# Connections.net
KiCad netlist of a schematic drawn in Altium Designer
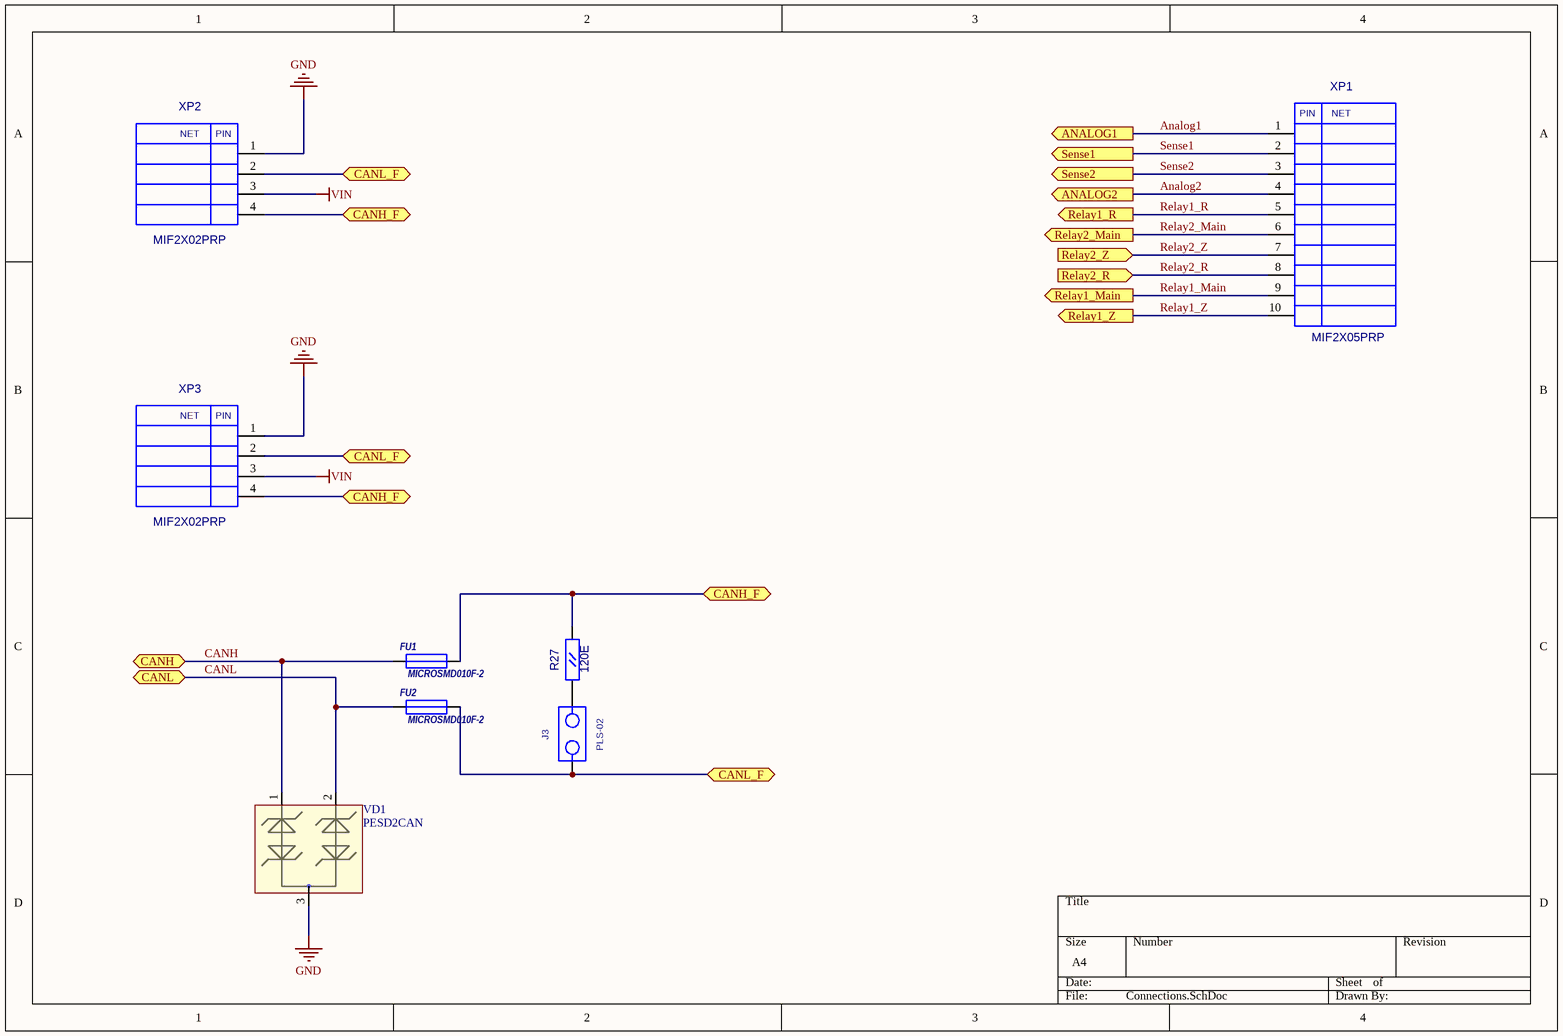
[diagram p0: Connections.SchDoc]

(export (version "E")
  (design (tool "Eeschema 10.0.6"))
  (components
    (comp (ref "FU1")
      (value "MICROSMD010F-2")
      (footprint "RC1210")
      (description "MICROSMD")
      (libsource (lib "gprs_modem_2") (part "MICROSMD"))
    )
    (comp (ref "FU2")
      (value "MICROSMD010F-2")
      (footprint "RC1210")
      (description "MICROSMD")
      (libsource (lib "gprs_modem_2") (part "MICROSMD"))
    )
    (comp (ref "J3") (value "PLS-02") (footprint "PLS-02") (libsource (lib "gprs_modem_2") (part "PLS-02")))
    (comp (ref "R27")
      (value "120E")
      (footprint "RC0805")
      (description "RC0805")
      (libsource (lib "gprs_modem_2") (part "RC0805"))
    )
    (comp (ref "VD1")
      (value "PESD2CAN")
      (footprint "SOT-23(123)")
      (description "TVS for CAN")
      (libsource (lib "gprs_modem_2") (part "PESD2CAN"))
    )
    (comp (ref "XP1")
      (value "MIF2X05PRP")
      (footprint "MIF2X05PRP")
      (libsource (lib "shlagbaum") (part "MIF2X05PRP"))
    )
    (comp (ref "XP2")
      (value "MIF2X02PRP")
      (footprint "MIF2X02PRP")
      (libsource (lib "gprs_modem_2") (part "MIF2X02PRP"))
    )
    (comp (ref "XP3")
      (value "MIF2X02PRP")
      (footprint "MIF2X02PRP")
      (libsource (lib "gprs_modem_2") (part "MIF2X02PRP"))
    )
  )
  (nets
    (net (code "1") (name "/Analog1") (class "Default")
      (node (ref "XP1") (pin "1") (pinfunction "1_1") (pintype "passive"))
    )
    (net (code "2") (name "/Analog2") (class "Default")
      (node (ref "XP1") (pin "4") (pinfunction "4_4") (pintype "passive"))
    )
    (net (code "3") (name "/CANH") (class "Default")
      (node (ref "FU1") (pin "1") (pintype "passive"))
      (node (ref "VD1") (pin "1") (pinfunction "1_1") (pintype "passive"))
    )
    (net (code "4") (name "/CANH_F") (class "Default")
      (node (ref "FU1") (pin "2") (pintype "passive"))
      (node (ref "R27") (pin "2") (pinfunction "B_2") (pintype "passive"))
      (node (ref "XP2") (pin "4") (pinfunction "4_4") (pintype "passive"))
      (node (ref "XP3") (pin "4") (pinfunction "4_4") (pintype "passive"))
    )
    (net (code "5") (name "/CANL") (class "Default")
      (node (ref "FU2") (pin "1") (pintype "passive"))
      (node (ref "VD1") (pin "2") (pinfunction "2_2") (pintype "passive"))
    )
    (net (code "6") (name "/CANL_F") (class "Default")
      (node (ref "FU2") (pin "2") (pintype "passive"))
      (node (ref "J3") (pin "1") (pintype "passive"))
      (node (ref "XP2") (pin "2") (pinfunction "2_2") (pintype "passive"))
      (node (ref "XP3") (pin "2") (pinfunction "2_2") (pintype "passive"))
    )
    (net (code "7") (name "/Relay1_Main") (class "Default")
      (node (ref "XP1") (pin "9") (pinfunction "9_9") (pintype "passive"))
    )
    (net (code "8") (name "/Relay1_R") (class "Default")
      (node (ref "XP1") (pin "5") (pinfunction "5_5") (pintype "passive"))
    )
    (net (code "9") (name "/Relay1_Z") (class "Default")
      (node (ref "XP1") (pin "10") (pinfunction "10_10") (pintype "passive"))
    )
    (net (code "10") (name "/Relay2_Main") (class "Default")
      (node (ref "XP1") (pin "6") (pinfunction "6_6") (pintype "passive"))
    )
    (net (code "11") (name "/Relay2_R") (class "Default")
      (node (ref "XP1") (pin "8") (pinfunction "8_8") (pintype "passive"))
    )
    (net (code "12") (name "/Relay2_Z") (class "Default")
      (node (ref "XP1") (pin "7") (pinfunction "7_7") (pintype "passive"))
    )
    (net (code "13") (name "/Sense1") (class "Default")
      (node (ref "XP1") (pin "2") (pinfunction "2_2") (pintype "passive"))
    )
    (net (code "14") (name "/Sense2") (class "Default")
      (node (ref "XP1") (pin "3") (pinfunction "3_3") (pintype "passive"))
    )
    (net (code "15") (name "GND") (class "Default")
      (node (ref "VD1") (pin "3") (pinfunction "3_3") (pintype "passive"))
      (node (ref "XP2") (pin "1") (pinfunction "1_1") (pintype "passive"))
      (node (ref "XP3") (pin "1") (pinfunction "1_1") (pintype "passive"))
    )
    (net (code "16") (name "Net-(R27-A)") (class "Default")
      (node (ref "J3") (pin "2") (pintype "passive"))
      (node (ref "R27") (pin "1") (pinfunction "A_1") (pintype "passive"))
    )
    (net (code "17") (name "VIN") (class "Default")
      (node (ref "XP2") (pin "3") (pinfunction "3_3") (pintype "passive"))
      (node (ref "XP3") (pin "3") (pinfunction "3_3") (pintype "passive"))
    )
  )
)
